# Voltage-Indicator.net
KiCad netlist of a schematic drawn in EAGLE
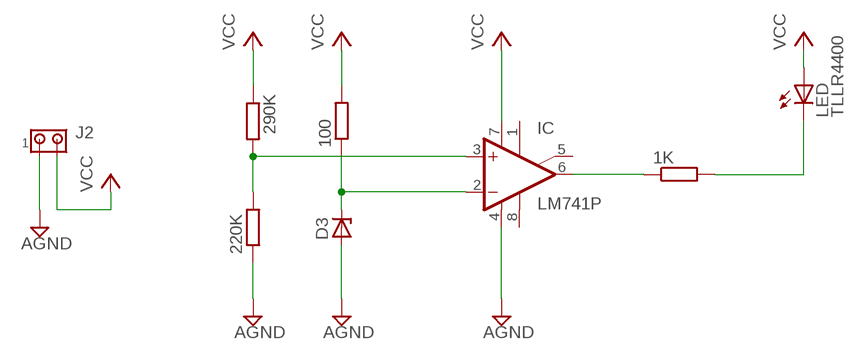
[diagram p0: schematic, sheet 1]

(export (version "E")
  (design (tool "Eeschema 10.0.6"))
  (components
    (comp (ref "1K")
      (value "R-EU_0204/7")
      (footprint "eagle-import:0204_7")
      (libsource (lib "eagle-import") (part "R-EU_0204/7"))
    )
    (comp (ref "100")
      (value "R-EU_0204/7")
      (footprint "eagle-import:0204_7")
      (libsource (lib "eagle-import") (part "R-EU_0204/7"))
    )
    (comp (ref "220K")
      (value "R-EU_0204/7")
      (footprint "eagle-import:0204_7")
      (libsource (lib "eagle-import") (part "R-EU_0204/7"))
    )
    (comp (ref "290K")
      (value "R-EU_0204/7")
      (footprint "eagle-import:0204_7")
      (libsource (lib "eagle-import") (part "R-EU_0204/7"))
    )
    (comp (ref "D3")
      (value "ZENER-DIODEDO35Z10")
      (footprint "eagle-import:DO35Z10")
      (libsource (lib "eagle-import") (part "ZENER-DIODEDO35Z10"))
    )
    (comp (ref "IC")
      (value "LM741P")
      (footprint "eagle-import:DIL08")
      (libsource (lib "eagle-import") (part "741PLM"))
    )
    (comp (ref "J2")
      (value "MTA02-100")
      (footprint "eagle-import:10X02MTA")
      (libsource (lib "eagle-import") (part "MTA02-100"))
    )
    (comp (ref "LED")
      (value "TLLR4400")
      (footprint "eagle-import:LED3MM")
      (fields (field (name "MF") "VISHAY SEMICONDUCTOR"))
      (libsource (lib "eagle-import") (part "TLLR4400"))
    )
  )
  (nets
    (net (code "1") (name "AGND") (class "Default")
      (node (ref "220K") (pin "1") (pinfunction "1_1") (pintype "passive"))
      (node (ref "D3") (pin "A") (pinfunction "A_A") (pintype "passive"))
      (node (ref "IC") (pin "4") (pinfunction "V-_4") (pintype "power_in"))
      (node (ref "J2") (pin "1") (pinfunction "1_1") (pintype "passive"))
    )
    (net (code "2") (name "Net-(IC-+IN)") (class "Default")
      (node (ref "220K") (pin "2") (pinfunction "2_2") (pintype "passive"))
      (node (ref "290K") (pin "2") (pinfunction "2_2") (pintype "passive"))
      (node (ref "IC") (pin "3") (pinfunction "+IN_3") (pintype "input"))
    )
    (net (code "3") (name "Net-(IC--IN)") (class "Default")
      (node (ref "100") (pin "1") (pinfunction "1_1") (pintype "passive"))
      (node (ref "D3") (pin "C") (pinfunction "C_C") (pintype "passive"))
      (node (ref "IC") (pin "2") (pinfunction "-IN_2") (pintype "input"))
    )
    (net (code "4") (name "Net-(IC-OUT)") (class "Default")
      (node (ref "1K") (pin "1") (pinfunction "1_1") (pintype "passive"))
      (node (ref "IC") (pin "6") (pinfunction "OUT_6") (pintype "output"))
    )
    (net (code "5") (name "Net-(LED-C)") (class "Default")
      (node (ref "1K") (pin "2") (pinfunction "2_2") (pintype "passive"))
      (node (ref "LED") (pin "K") (pinfunction "C_K") (pintype "passive"))
    )
    (net (code "6") (name "VCC") (class "Default")
      (node (ref "100") (pin "2") (pinfunction "2_2") (pintype "passive"))
      (node (ref "290K") (pin "1") (pinfunction "1_1") (pintype "passive"))
      (node (ref "IC") (pin "7") (pinfunction "V+_7") (pintype "power_in"))
      (node (ref "J2") (pin "2") (pinfunction "2_2") (pintype "passive"))
      (node (ref "LED") (pin "A") (pinfunction "A_A") (pintype "passive"))
    )
    (net (code "7") (name "unconnected-(IC-ON1-Pad1)") (class "Default")
      (node (ref "IC") (pin "1") (pinfunction "ON1_1") (pintype "passive"))
    )
    (net (code "8") (name "unconnected-(IC-ON2-Pad5)") (class "Default")
      (node (ref "IC") (pin "5") (pinfunction "ON2_5") (pintype "passive"))
    )
    (net (code "9") (name "unconnected-(IC-OPT-Pad8)") (class "Default")
      (node (ref "IC") (pin "8") (pinfunction "OPT_8") (pintype "passive"))
    )
  )
)
